# Power_management.net
KiCad netlist of a schematic drawn in Altium Designer
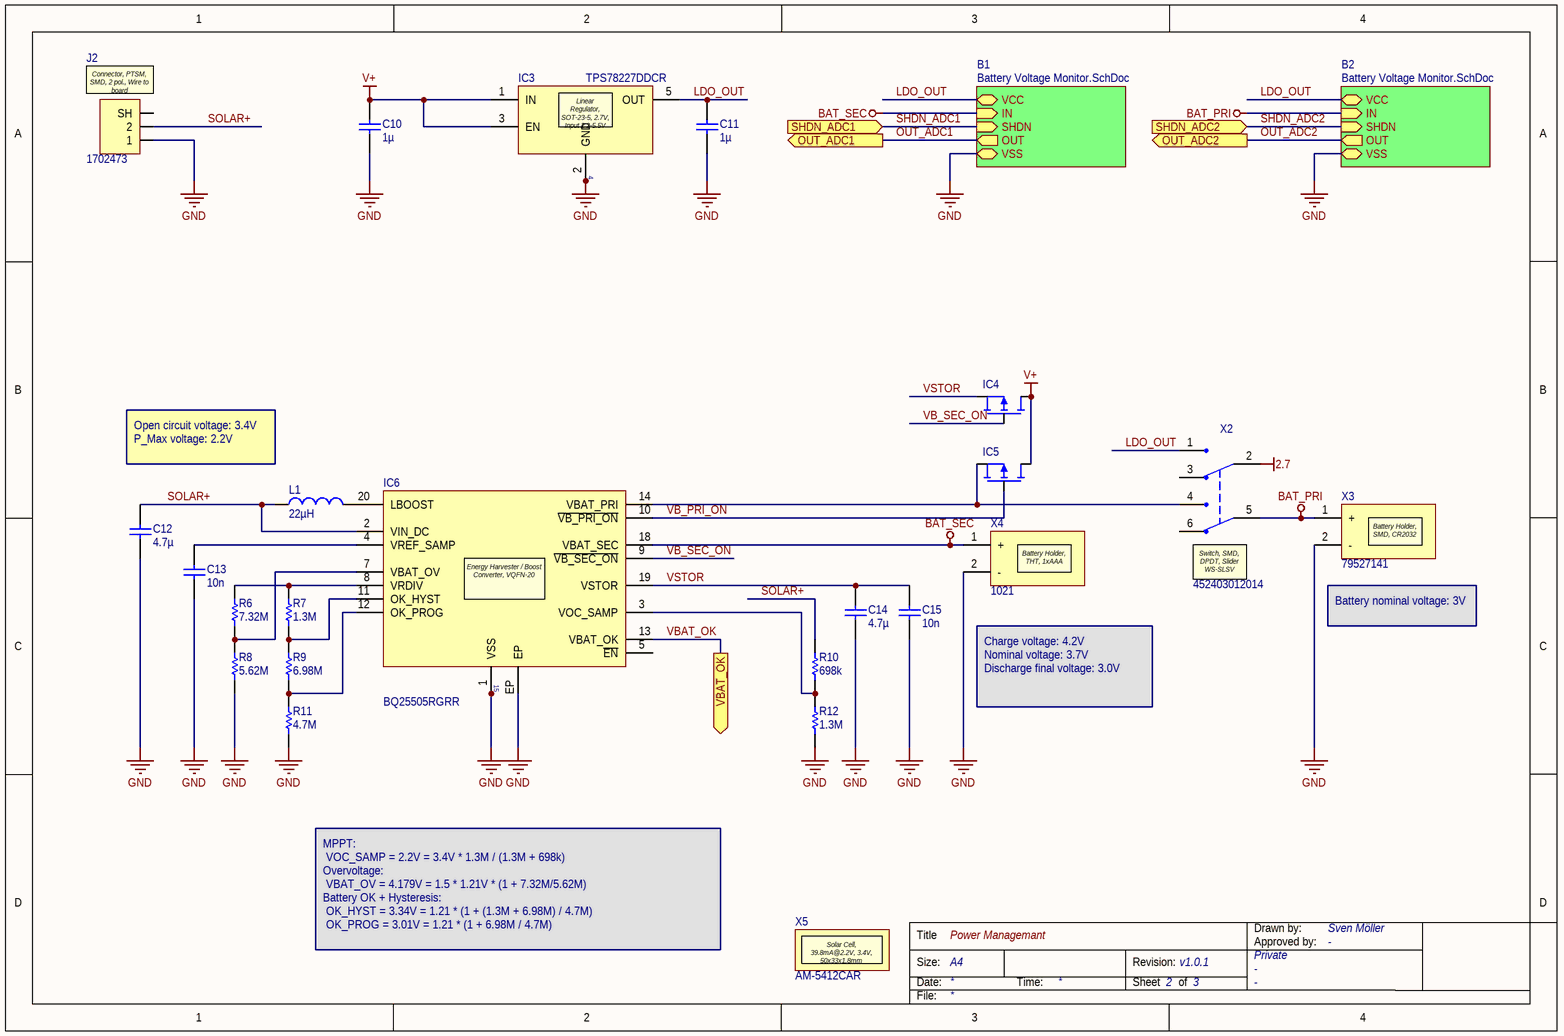
[diagram p0: Power management.SchDoc]

(export (version "E")
  (design (tool "Eeschema 10.0.6"))
  (components
    (comp (ref "C10")
      (value "1µ")
      (footprint "C0805")
      (description "Cap, 1µ, 0805, 50V, X7R")
      (fields (field (name "MPN") "GRM21BR71H105KA12L") (field (name "MANUFACTURER") "Murata"))
      (libsource (lib "Createc Circuitstudio Library") (part "GRM21BR71H105KA12L"))
    )
    (comp (ref "C11")
      (value "1µ")
      (footprint "C0805")
      (description "Cap, 1µ, 0805, 50V, X7R")
      (fields (field (name "MPN") "GRM21BR71H105KA12L") (field (name "MANUFACTURER") "Murata"))
      (libsource (lib "Createc Circuitstudio Library") (part "GRM21BR71H105KA12L"))
    )
    (comp (ref "C12")
      (value "4.7µ")
      (footprint "C0603")
      (description "Cap, 4.7µ, 0603, X5R, 10V")
      (fields (field (name "MPN") "C0603C475M8PACTU") (field (name "MANUFACTURER") "Kemet"))
      (libsource (lib "Schlib1") (part "C0603C475M8PACTU"))
    )
    (comp (ref "C13")
      (value "10n")
      (footprint "C0603")
      (description "Cap, 10n, 0603, C0G, 25V")
      (fields (field (name "MPN") "C0603C103J3GACTU") (field (name "MANUFACTURER") "Kemet"))
      (libsource (lib "Schlib1") (part "C0603C103J3GACTU"))
    )
    (comp (ref "C14")
      (value "4.7µ")
      (footprint "C0603")
      (description "Cap, 4.7µ, 0603, X5R, 10V")
      (fields (field (name "MPN") "C0603C475M8PACTU") (field (name "MANUFACTURER") "Kemet"))
      (libsource (lib "Schlib1") (part "C0603C475M8PACTU"))
    )
    (comp (ref "C15")
      (value "10n")
      (footprint "C0603")
      (description "Cap, 10n, 0603, C0G, 25V")
      (fields (field (name "MPN") "C0603C103J3GACTU") (field (name "MANUFACTURER") "Kemet"))
      (libsource (lib "Schlib1") (part "C0603C103J3GACTU"))
    )
    (comp (ref "IC3")
      (value "TPS78227DDCR")
      (footprint "SOT-23-5")
      (description "Linear Regulator, SOT-23-5, 2.7V, Input 2.2-5.5V")
      (fields (field (name "MANUFACTURER") "Texas Instruments") (field (name "MPN") "TPS78227DDCR"))
      (libsource (lib "Schlib1") (part "TPS78227DDCR"))
    )
    (comp (ref "IC4")
      (value "PMZ950UPEL")
      (footprint "SOT-883")
      (description "MOSFET, SOT-883, p-channel, -20V, -0.5A, low leakage current")
      (fields (field (name "MANUFACTURER") "Nexperia"))
      (libsource (lib "Schlib1") (part "PMZ950UPEL"))
    )
    (comp (ref "IC5")
      (value "PMZ950UPEL")
      (footprint "SOT-883")
      (description "MOSFET, SOT-883, p-channel, -20V, -0.5A, low leakage current")
      (fields (field (name "MANUFACTURER") "Nexperia"))
      (libsource (lib "Schlib1") (part "PMZ950UPEL"))
    )
    (comp (ref "IC6")
      (value "BQ25505RGRR")
      (footprint "VQFN-20-EP_3.5x3.5")
      (description "Energy Harvester / Boost Converter, VQFN-20")
      (fields (field (name "MANUFACTURER") "Texas Instruments") (field (name "MPN") "BQ25505RGRR"))
      (libsource (lib "Schlib1") (part "BQ25505RGRR"))
    )
    (comp (ref "J2")
      (value "1702473")
      (footprint "1702473")
      (description "Connector, PTSM, SMD, 2 pol., Wire to board")
      (fields (field (name "MANUFACTURER") "Phoenix Contact") (field (name "MPN") "1702473"))
      (libsource (lib "Schlib1") (part "1702473"))
    )
    (comp (ref "L1")
      (value "22µH")
      (footprint "WE-TCP_3816")
      (description "Ind, 22µH, 0.51A, 3.8x3.8x1.65mm")
      (fields (field (name "MANUFACTURER") "Würth Elektronik") (field (name "MPN") "744031220"))
      (libsource (lib "Schlib1") (part "744031220"))
    )
    (comp (ref "R6")
      (value "7.32M")
      (footprint "R0603")
      (description "Res, 7.32M, 0603, 1%, 75V, 100mW")
      (fields (field (name "TOLERANCE") "1%") (field (name "MPN") "CRCW06037M32FKEA"))
      (libsource (lib "Schlib1") (part "CRCW06037M32FKEA"))
    )
    (comp (ref "R7")
      (value "1.3M")
      (footprint "R0603")
      (description "Res, 1.3M, 0603, 1%, 75V, 100mW")
      (fields (field (name "TOLERANCE") "1%") (field (name "MPN") "CRCW06031M30FKEA"))
      (libsource (lib "Schlib1") (part "CRCW06031M30FKEA"))
    )
    (comp (ref "R8")
      (value "5.62M")
      (footprint "R0603")
      (description "Res, 5.62M, 0603, 1%, 75V, 100mW")
      (fields (field (name "TOLERANCE") "1%") (field (name "MPN") "CRCW06035M62FKEA"))
      (libsource (lib "Schlib1") (part "CRCW06035M62FKEA"))
    )
    (comp (ref "R9")
      (value "6.98M")
      (footprint "R0603")
      (description "Res, 6.98M, 0603, 1%, 75V, 100mW")
      (fields (field (name "TOLERANCE") "1%") (field (name "MPN") "CRCW06036M98FKEA"))
      (libsource (lib "Schlib1") (part "CRCW06036M98FKEA"))
    )
    (comp (ref "R10")
      (value "698k")
      (footprint "R0603")
      (description "Res, 698k, 0603, 1%, 75V, 100mW")
      (fields (field (name "TOLERANCE") "1%") (field (name "MPN") "ERJ-3EKF6983V"))
      (libsource (lib "Schlib1") (part "ERJ-3EKF6983V"))
    )
    (comp (ref "R11")
      (value "4.7M")
      (footprint "R0603")
      (description "Res, 4.7M, 0603, 1%, 75V, 100mW")
      (fields (field (name "TOLERANCE") "1%") (field (name "MPN") "CRCW06034M70FKEA"))
      (libsource (lib "Schlib1") (part "CRCW06034M70FKEA"))
    )
    (comp (ref "R12")
      (value "1.3M")
      (footprint "R0603")
      (description "Res, 1.3M, 0603, 1%, 75V, 100mW")
      (fields (field (name "TOLERANCE") "1%") (field (name "MPN") "CRCW06031M30FKEA"))
      (libsource (lib "Schlib1") (part "CRCW06031M30FKEA"))
    )
    (comp (ref "X2")
      (value "452403012014")
      (footprint "452403012014")
      (description "Switch, SMD, DPDT, Slider WS-SLSV")
      (fields (field (name "MANUFACTURER") "Würth Elektronik") (field (name "MPN") "452403012014"))
      (libsource (lib "Schlib1") (part "452403012014"))
    )
    (comp (ref "X3")
      (value "79527141")
      (footprint "79527141")
      (description "Battery Holder, SMD, CR2032")
      (fields (field (name "MANUFACTURER") "Würth Elektronik") (field (name "MPN") "79527141"))
      (libsource (lib "Schlib1") (part "79527141"))
    )
    (comp (ref "X4")
      (value "Keystone_Electronics_1021")
      (footprint "Keystone_Electronics_1021")
      (description "Battery Holder, THT, 1xAAA")
      (fields (field (name "MANUFACTURER") "Keystone Electronics") (field (name "MPN") "1021"))
      (libsource (lib "Schlib1") (part "Keystone_Electronics_1021"))
    )
    (comp (ref "X5")
      (value "AM-5412CAR")
      (footprint "AM-5412CAR")
      (description "Solar Cell, 39.8mA@2.2V, 3.4V, 50x33x1.8mm")
      (fields (field (name "MANUFACTURER") "Panasonic BSG") (field (name "MPN") "AM-5412CAR"))
      (libsource (lib "Schlib1") (part "AM-5412CAR"))
    )
  )
  (nets
    (net (code "1") (name "/LDO_OUT") (class "Default")
      (node (ref "C11") (pin "2") (pinfunction "2_2") (pintype "passive"))
      (node (ref "IC3") (pin "5") (pinfunction "OUT_5") (pintype "passive"))
      (node (ref "X2") (pin "1") (pinfunction "NO1_1") (pintype "passive"))
    )
    (net (code "6") (name "/SOLAR+") (class "Default")
      (node (ref "C12") (pin "2") (pinfunction "2_2") (pintype "passive"))
      (node (ref "IC6") (pin "2") (pinfunction "VIN_DC_2") (pintype "passive"))
      (node (ref "J2") (pin "2") (pinfunction "2_2") (pintype "passive"))
      (node (ref "L1") (pin "1") (pinfunction "1_1") (pintype "passive"))
      (node (ref "R10") (pin "2") (pinfunction "2_2") (pintype "passive"))
    )
    (net (code "7") (name "/VBAT_OK") (class "Default")
      (node (ref "IC6") (pin "13") (pinfunction "VBAT_OK_13") (pintype "passive"))
    )
    (net (code "8") (name "/VB_PRI_ON") (class "Default")
      (node (ref "IC5") (pin "1") (pinfunction "G_1") (pintype "passive"))
      (node (ref "IC6") (pin "10") (pinfunction "~{VB_PRI_ON}_10") (pintype "passive"))
    )
    (net (code "9") (name "/VB_SEC_ON") (class "Default")
      (node (ref "IC4") (pin "1") (pinfunction "G_1") (pintype "passive"))
      (node (ref "IC6") (pin "9") (pinfunction "~{VB_SEC_ON}_9") (pintype "passive"))
    )
    (net (code "10") (name "/VSTOR") (class "Default")
      (node (ref "C14") (pin "2") (pinfunction "2_2") (pintype "passive"))
      (node (ref "C15") (pin "2") (pinfunction "2_2") (pintype "passive"))
      (node (ref "IC4") (pin "2") (pinfunction "S_2") (pintype "passive"))
      (node (ref "IC6") (pin "19") (pinfunction "VSTOR_19") (pintype "passive"))
    )
    (net (code "11") (name "2.7") (class "Default")
      (node (ref "X2") (pin "2") (pinfunction "COM1_2") (pintype "passive"))
    )
    (net (code "12") (name "BAT_PRI") (class "Default")
      (node (ref "X2") (pin "5") (pinfunction "COM2_5") (pintype "passive"))
      (node (ref "X3") (pin "1") (pinfunction "+_1") (pintype "passive"))
    )
    (net (code "13") (name "BAT_SEC") (class "Default")
      (node (ref "IC6") (pin "18") (pinfunction "VBAT_SEC_18") (pintype "passive"))
      (node (ref "X4") (pin "1") (pinfunction "+_1") (pintype "passive"))
    )
    (net (code "14") (name "GND") (class "Default")
      (node (ref "C10") (pin "1") (pinfunction "1_1") (pintype "passive"))
      (node (ref "C11") (pin "1") (pinfunction "1_1") (pintype "passive"))
      (node (ref "C12") (pin "1") (pinfunction "1_1") (pintype "passive"))
      (node (ref "C13") (pin "1") (pinfunction "1_1") (pintype "passive"))
      (node (ref "C14") (pin "1") (pinfunction "1_1") (pintype "passive"))
      (node (ref "C15") (pin "1") (pinfunction "1_1") (pintype "passive"))
      (node (ref "IC3") (pin "2") (pinfunction "GND_2") (pintype "passive"))
      (node (ref "IC3") (pin "4") (pinfunction "GND_4") (pintype "passive"))
      (node (ref "IC6") (pin "1") (pinfunction "VSS_1") (pintype "passive"))
      (node (ref "IC6") (pin "15") (pinfunction "VSS_15") (pintype "passive"))
      (node (ref "IC6") (pin "EP") (pinfunction "EP_EP") (pintype "passive"))
      (node (ref "J2") (pin "1") (pinfunction "1_1") (pintype "passive"))
      (node (ref "R11") (pin "1") (pinfunction "1_1") (pintype "passive"))
      (node (ref "R12") (pin "1") (pinfunction "1_1") (pintype "passive"))
      (node (ref "R8") (pin "1") (pinfunction "1_1") (pintype "passive"))
      (node (ref "X3") (pin "2") (pinfunction "-_2") (pintype "passive"))
      (node (ref "X4") (pin "2") (pinfunction "-_2") (pintype "passive"))
    )
    (net (code "15") (name "Net-(IC5-S)") (class "Default")
      (node (ref "IC5") (pin "2") (pinfunction "S_2") (pintype "passive"))
      (node (ref "IC6") (pin "14") (pinfunction "VBAT_PRI_14") (pintype "passive"))
      (node (ref "X2") (pin "4") (pinfunction "NO2_4") (pintype "passive"))
    )
    (net (code "16") (name "Net-(IC6-LBOOST)") (class "Default")
      (node (ref "IC6") (pin "20") (pinfunction "LBOOST_20") (pintype "passive"))
      (node (ref "L1") (pin "2") (pinfunction "2_2") (pintype "passive"))
    )
    (net (code "17") (name "Net-(IC6-OK_HYST)") (class "Default")
      (node (ref "IC6") (pin "11") (pinfunction "OK_HYST_11") (pintype "passive"))
      (node (ref "R7") (pin "1") (pinfunction "1_1") (pintype "passive"))
      (node (ref "R9") (pin "2") (pinfunction "2_2") (pintype "passive"))
    )
    (net (code "18") (name "Net-(IC6-OK_PROG)") (class "Default")
      (node (ref "IC6") (pin "12") (pinfunction "OK_PROG_12") (pintype "passive"))
      (node (ref "R11") (pin "2") (pinfunction "2_2") (pintype "passive"))
      (node (ref "R9") (pin "1") (pinfunction "1_1") (pintype "passive"))
    )
    (net (code "19") (name "Net-(IC6-VBAT_OV)") (class "Default")
      (node (ref "IC6") (pin "7") (pinfunction "VBAT_OV_7") (pintype "passive"))
      (node (ref "R6") (pin "1") (pinfunction "1_1") (pintype "passive"))
      (node (ref "R8") (pin "2") (pinfunction "2_2") (pintype "passive"))
    )
    (net (code "20") (name "Net-(IC6-VOC_SAMP)") (class "Default")
      (node (ref "IC6") (pin "3") (pinfunction "VOC_SAMP_3") (pintype "passive"))
      (node (ref "R10") (pin "1") (pinfunction "1_1") (pintype "passive"))
      (node (ref "R12") (pin "2") (pinfunction "2_2") (pintype "passive"))
    )
    (net (code "21") (name "Net-(IC6-VRDIV)") (class "Default")
      (node (ref "IC6") (pin "8") (pinfunction "VRDIV_8") (pintype "passive"))
      (node (ref "R6") (pin "2") (pinfunction "2_2") (pintype "passive"))
      (node (ref "R7") (pin "2") (pinfunction "2_2") (pintype "passive"))
    )
    (net (code "22") (name "Net-(IC6-VREF_SAMP)") (class "Default")
      (node (ref "C13") (pin "2") (pinfunction "2_2") (pintype "passive"))
      (node (ref "IC6") (pin "4") (pinfunction "VREF_SAMP_4") (pintype "passive"))
    )
    (net (code "23") (name "Net-(J2-SH)") (class "Default")
      (node (ref "J2") (pin "SH1") (pinfunction "SH_SH1") (pintype "passive"))
      (node (ref "J2") (pin "SH2") (pinfunction "SH2_SH2") (pintype "passive"))
    )
    (net (code "24") (name "V+") (class "Default")
      (node (ref "C10") (pin "2") (pinfunction "2_2") (pintype "passive"))
      (node (ref "IC3") (pin "1") (pinfunction "IN_1") (pintype "passive"))
      (node (ref "IC3") (pin "3") (pinfunction "EN_3") (pintype "passive"))
      (node (ref "IC4") (pin "3") (pinfunction "D_3") (pintype "passive"))
      (node (ref "IC5") (pin "3") (pinfunction "D_3") (pintype "passive"))
    )
    (net (code "25") (name "unconnected-(IC6-~{EN}-Pad5)") (class "Default")
      (node (ref "IC6") (pin "5") (pinfunction "~{EN}_5") (pintype "passive"))
    )
    (net (code "26") (name "unconnected-(X2-NC1-Pad3)") (class "Default")
      (node (ref "X2") (pin "3") (pinfunction "NC1_3") (pintype "passive"))
    )
    (net (code "27") (name "unconnected-(X2-NC2-Pad6)") (class "Default")
      (node (ref "X2") (pin "6") (pinfunction "NC2_6") (pintype "passive"))
    )
  )
)
